# StepperDriver.net
KiCad netlist of a schematic drawn in Altium Designer
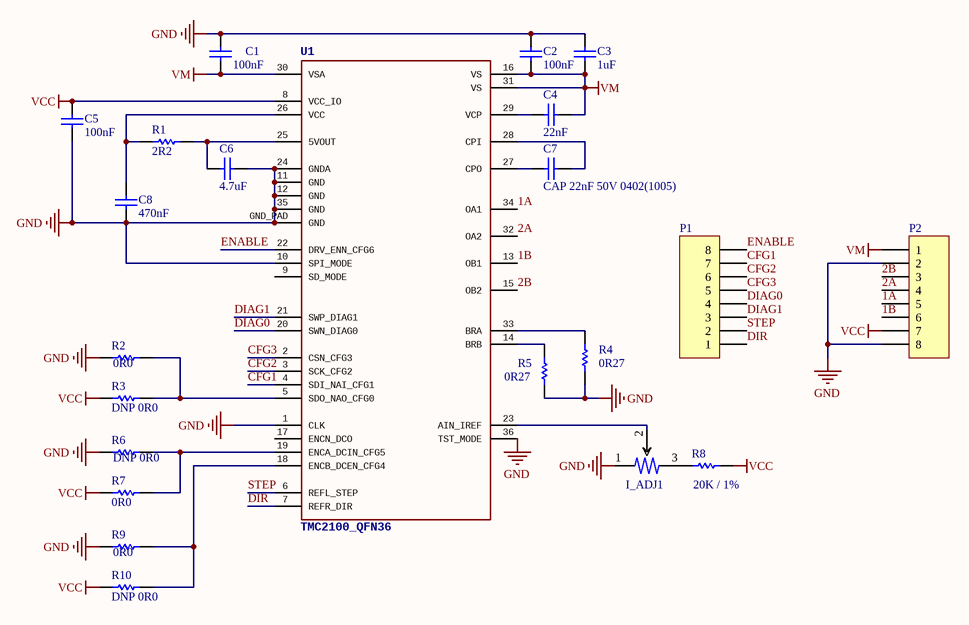
[diagram p0: StepperDriver.SchDoc]

(export (version "E")
  (design (tool "Eeschema 10.0.6"))
  (components
    (comp (ref "C1")
      (value "100nF")
      (footprint "CAPC0402(1005)60_M")
      (description "CAP 100nF 50V ±10% 0402 (1005 Metric) Thickness 0.6mm SMD")
      (fields (field (name "TOLERANCE") "Â±10%"))
      (libsource (lib "Altium Content Vault") (part "CAP"))
    )
    (comp (ref "C2")
      (value "100nF")
      (footprint "CAPC0402(1005)60_M")
      (description "CAP 100nF 50V ±10% 0402 (1005 Metric) Thickness 0.6mm SMD")
      (fields (field (name "TOLERANCE") "Â±10%"))
      (libsource (lib "Altium Content Vault") (part "CAP"))
    )
    (comp (ref "C3")
      (value "1uF")
      (footprint "CAPC0603(1608)100_L")
      (description "CAP 1uF 50V ±10% 0603 (1608 Metric) Thickness 1mm SMD")
      (fields (field (name "TOLERANCE") "Â±10%"))
      (libsource (lib "Altium Content Vault") (part "CAP"))
    )
    (comp (ref "C4")
      (value "22nF")
      (footprint "CAPC0402(1005)60_L")
      (description "CAP 22nF 50V ±5% 0402 (1005 Metric) Thickness 0.6mm SMD")
      (fields (field (name "TOLERANCE") "Â±5%"))
      (libsource (lib "Altium Content Vault") (part "CAP"))
    )
    (comp (ref "C5")
      (value "100nF")
      (footprint "CAPC0402(1005)60_M")
      (description "CAP 100nF 50V ±10% 0402 (1005 Metric) Thickness 0.6mm SMD")
      (fields (field (name "TOLERANCE") "Â±10%"))
      (libsource (lib "Altium Content Vault") (part "CAP"))
    )
    (comp (ref "C6")
      (value "4.7uF")
      (footprint "CAPC0402(1005)60_N")
      (description "CAP 2.2uF 10V ±10% 0402 (1005 Metric) Thickness 0.6mm SMD")
      (fields (field (name "TOLERANCE") "Â±10%"))
      (libsource (lib "Altium Content Vault") (part "CAP"))
    )
    (comp (ref "C7")
      (value "CAP 22nF 50V 0402(1005)")
      (footprint "CAPC0402(1005)60_L")
      (description "CAP 22nF 50V ±5% 0402 (1005 Metric) Thickness 0.6mm SMD")
      (fields (field (name "TOLERANCE") "Â±5%"))
      (libsource (lib "Altium Content Vault") (part "CAP"))
    )
    (comp (ref "C8")
      (value "470nF")
      (footprint "CAPC0402(1005)60_N")
      (description "CAP 470nF 10V ±10% 0402 (1005 Metric) Thickness 0.6mm SMD")
      (fields (field (name "TOLERANCE") "Â±10%"))
      (libsource (lib "Altium Content Vault") (part "CAP"))
    )
    (comp (ref "I_ADJ1")
      (value "PVZ3A Trimmer")
      (footprint "PVZ3A")
      (libsource (lib "Components") (part "PVZ3A Trimmer"))
    )
    (comp (ref "P1")
      (value "Header 8")
      (footprint "HDR1X8")
      (description "Header, 8-Pin")
      (fields (field (name "PUBLISHER") "Altium Limited"))
      (libsource (lib "Miscellaneous Connectors") (part "Header 8"))
    )
    (comp (ref "P2")
      (value "Header 8")
      (footprint "HDR1X8")
      (description "Header, 8-Pin")
      (fields (field (name "PUBLISHER") "Altium Limited"))
      (libsource (lib "") (part "Header 8_1"))
    )
    (comp (ref "R1")
      (value "2R2")
      (footprint "RESC0402(1005)_N")
      (description "2R2 0.063W 5% 0402 (1005 Metric)  SMD")
      (fields (field (name "TOLERANCE") "5 %") (field (name "POWER") "0.063 W"))
      (libsource (lib "Altium Content Vault") (part "RES"))
    )
    (comp (ref "R2")
      (value "0R0")
      (footprint "RESC0402(1005)_M")
      (description "Jumper 0402 (1005 Metric)")
      (fields (field (name "TOLERANCE") "None"))
      (libsource (lib "Altium Content Vault") (part "RES"))
    )
    (comp (ref "R3")
      (value "DNP 0R0")
      (footprint "RESC0402(1005)_M")
      (description "Jumper 0402 (1005 Metric)")
      (fields (field (name "TOLERANCE") "None"))
      (libsource (lib "Altium Content Vault") (part "RES"))
    )
    (comp (ref "R4")
      (value "0R27")
      (footprint "RESC0805(2012)_N")
      (description "Jumper 0805 (2012 Metric)")
      (fields (field (name "TOLERANCE") "None"))
      (libsource (lib "Altium Content Vault") (part "RES"))
    )
    (comp (ref "R5")
      (value "0R27")
      (footprint "RESC0805(2012)_N")
      (description "Jumper 0805 (2012 Metric)")
      (fields (field (name "TOLERANCE") "None"))
      (libsource (lib "Altium Content Vault") (part "RES"))
    )
    (comp (ref "R6")
      (value "DNP 0R0")
      (footprint "RESC0402(1005)_M")
      (description "Jumper 0402 (1005 Metric)")
      (fields (field (name "TOLERANCE") "None"))
      (libsource (lib "Altium Content Vault") (part "RES"))
    )
    (comp (ref "R7")
      (value "0R0")
      (footprint "RESC0402(1005)_M")
      (description "Jumper 0402 (1005 Metric)")
      (fields (field (name "TOLERANCE") "None"))
      (libsource (lib "Altium Content Vault") (part "RES"))
    )
    (comp (ref "R8")
      (value "20K / 1%")
      (footprint "RESC0402(1005)_L")
      (description "0402 (1005 Metric) Chip Resistor")
      (libsource (lib "Altium Content Vault") (part "CMP-1591-00004-1"))
    )
    (comp (ref "R9")
      (value "0R0")
      (footprint "RESC0402(1005)_M")
      (description "Jumper 0402 (1005 Metric)")
      (fields (field (name "TOLERANCE") "None"))
      (libsource (lib "Altium Content Vault") (part "RES"))
    )
    (comp (ref "R10")
      (value "DNP 0R0")
      (footprint "RESC0402(1005)_M")
      (description "Jumper 0402 (1005 Metric)")
      (fields (field (name "TOLERANCE") "None"))
      (libsource (lib "Altium Content Vault") (part "RES"))
    )
    (comp (ref "U1")
      (value "TMC2100_QFN36")
      (footprint "QFN36")
      (libsource (lib "Components") (part "TMC2100_QFN36"))
    )
  )
  (nets
    (net (code "1") (name "/1A") (class "Default")
      (node (ref "P2") (pin "5") (pinfunction "5_5") (pintype "passive"))
      (node (ref "U1") (pin "34") (pinfunction "OA1_34") (pintype "passive"))
    )
    (net (code "2") (name "/1B") (class "Default")
      (node (ref "P2") (pin "6") (pinfunction "6_6") (pintype "passive"))
      (node (ref "U1") (pin "13") (pinfunction "OB1_13") (pintype "passive"))
    )
    (net (code "3") (name "/2A") (class "Default")
      (node (ref "P2") (pin "4") (pinfunction "4_4") (pintype "passive"))
      (node (ref "U1") (pin "32") (pinfunction "OA2_32") (pintype "passive"))
    )
    (net (code "4") (name "/2B") (class "Default")
      (node (ref "P2") (pin "3") (pinfunction "3_3") (pintype "passive"))
      (node (ref "U1") (pin "15") (pinfunction "OB2_15") (pintype "passive"))
    )
    (net (code "5") (name "/CFG1") (class "Default")
      (node (ref "P1") (pin "7") (pinfunction "7_7") (pintype "passive"))
      (node (ref "U1") (pin "4") (pinfunction "SDI_NAI_CFG1_4") (pintype "passive"))
    )
    (net (code "6") (name "/CFG2") (class "Default")
      (node (ref "P1") (pin "6") (pinfunction "6_6") (pintype "passive"))
      (node (ref "U1") (pin "3") (pinfunction "SCK_CFG2_3") (pintype "passive"))
    )
    (net (code "7") (name "/CFG3") (class "Default")
      (node (ref "P1") (pin "5") (pinfunction "5_5") (pintype "passive"))
      (node (ref "U1") (pin "2") (pinfunction "CSN_CFG3_2") (pintype "passive"))
    )
    (net (code "8") (name "/DIAG0") (class "Default")
      (node (ref "P1") (pin "4") (pinfunction "4_4") (pintype "passive"))
      (node (ref "U1") (pin "20") (pinfunction "SWN_DIAG0_20") (pintype "passive"))
    )
    (net (code "9") (name "/DIAG1") (class "Default")
      (node (ref "P1") (pin "3") (pinfunction "3_3") (pintype "passive"))
      (node (ref "U1") (pin "21") (pinfunction "SWP_DIAG1_21") (pintype "passive"))
    )
    (net (code "10") (name "/DIR") (class "Default")
      (node (ref "P1") (pin "1") (pinfunction "1_1") (pintype "passive"))
      (node (ref "U1") (pin "7") (pinfunction "REFR_DIR_7") (pintype "passive"))
    )
    (net (code "11") (name "/ENABLE") (class "Default")
      (node (ref "P1") (pin "8") (pinfunction "8_8") (pintype "passive"))
      (node (ref "U1") (pin "22") (pinfunction "DRV_ENN_CFG6_22") (pintype "passive"))
    )
    (net (code "12") (name "/STEP") (class "Default")
      (node (ref "P1") (pin "2") (pinfunction "2_2") (pintype "passive"))
      (node (ref "U1") (pin "6") (pinfunction "REFL_STEP_6") (pintype "passive"))
    )
    (net (code "13") (name "GND") (class "Default")
      (node (ref "C1") (pin "2") (pinfunction "2_2") (pintype "passive"))
      (node (ref "C2") (pin "2") (pinfunction "2_2") (pintype "passive"))
      (node (ref "C3") (pin "2") (pinfunction "2_2") (pintype "passive"))
      (node (ref "C5") (pin "1") (pinfunction "1_1") (pintype "passive"))
      (node (ref "C6") (pin "1") (pinfunction "1_1") (pintype "passive"))
      (node (ref "C8") (pin "1") (pinfunction "1_1") (pintype "passive"))
      (node (ref "I_ADJ1") (pin "1") (pinfunction "CCW_1") (pintype "passive"))
      (node (ref "P2") (pin "2") (pinfunction "2_2") (pintype "passive"))
      (node (ref "P2") (pin "8") (pinfunction "8_8") (pintype "passive"))
      (node (ref "R2") (pin "1") (pinfunction "1_1") (pintype "passive"))
      (node (ref "R4") (pin "1") (pinfunction "1_1") (pintype "passive"))
      (node (ref "R5") (pin "1") (pinfunction "1_1") (pintype "passive"))
      (node (ref "R6") (pin "1") (pinfunction "1_1") (pintype "passive"))
      (node (ref "R9") (pin "1") (pinfunction "1_1") (pintype "passive"))
      (node (ref "U1") (pin "1") (pinfunction "CLK_1") (pintype "passive"))
      (node (ref "U1") (pin "10") (pinfunction "SPI_MODE_10") (pintype "passive"))
      (node (ref "U1") (pin "11") (pinfunction "GND_11") (pintype "passive"))
      (node (ref "U1") (pin "12") (pinfunction "GND_12") (pintype "passive"))
      (node (ref "U1") (pin "24") (pinfunction "GNDA_24") (pintype "passive"))
      (node (ref "U1") (pin "35") (pinfunction "GND_35") (pintype "passive"))
      (node (ref "U1") (pin "36") (pinfunction "TST_MODE_36") (pintype "passive"))
      (node (ref "U1") (pin "GND_PAD") (pinfunction "GND_GND_PAD") (pintype "passive"))
    )
    (net (code "14") (name "Net-(I_ADJ1-CW)") (class "Default")
      (node (ref "I_ADJ1") (pin "3") (pinfunction "CW_3") (pintype "passive"))
      (node (ref "R8") (pin "1") (pinfunction "1_1") (pintype "passive"))
    )
    (net (code "15") (name "Net-(I_ADJ1-OUT)") (class "Default")
      (node (ref "I_ADJ1") (pin "2") (pinfunction "OUT_2") (pintype "passive"))
      (node (ref "U1") (pin "23") (pinfunction "AIN_IREF_23") (pintype "passive"))
    )
    (net (code "16") (name "Net-(U1-5VOUT)") (class "Default")
      (node (ref "C6") (pin "2") (pinfunction "2_2") (pintype "passive"))
      (node (ref "R1") (pin "2") (pinfunction "2_2") (pintype "passive"))
      (node (ref "U1") (pin "25") (pinfunction "5VOUT_25") (pintype "passive"))
    )
    (net (code "17") (name "Net-(U1-BRA)") (class "Default")
      (node (ref "R4") (pin "2") (pinfunction "2_2") (pintype "passive"))
      (node (ref "U1") (pin "33") (pinfunction "BRA_33") (pintype "passive"))
    )
    (net (code "18") (name "Net-(U1-BRB)") (class "Default")
      (node (ref "R5") (pin "2") (pinfunction "2_2") (pintype "passive"))
      (node (ref "U1") (pin "14") (pinfunction "BRB_14") (pintype "passive"))
    )
    (net (code "19") (name "Net-(U1-CPI)") (class "Default")
      (node (ref "C7") (pin "1") (pinfunction "1_1") (pintype "passive"))
      (node (ref "U1") (pin "28") (pinfunction "CPI_28") (pintype "passive"))
    )
    (net (code "20") (name "Net-(U1-CPO)") (class "Default")
      (node (ref "C7") (pin "2") (pinfunction "2_2") (pintype "passive"))
      (node (ref "U1") (pin "27") (pinfunction "CPO_27") (pintype "passive"))
    )
    (net (code "21") (name "Net-(U1-ENCA_DCIN_CFG5)") (class "Default")
      (node (ref "R6") (pin "2") (pinfunction "2_2") (pintype "passive"))
      (node (ref "R7") (pin "2") (pinfunction "2_2") (pintype "passive"))
      (node (ref "U1") (pin "19") (pinfunction "ENCA_DCIN_CFG5_19") (pintype "passive"))
    )
    (net (code "22") (name "Net-(U1-ENCB_DCEN_CFG4)") (class "Default")
      (node (ref "R10") (pin "2") (pinfunction "2_2") (pintype "passive"))
      (node (ref "R9") (pin "2") (pinfunction "2_2") (pintype "passive"))
      (node (ref "U1") (pin "18") (pinfunction "ENCB_DCEN_CFG4_18") (pintype "passive"))
    )
    (net (code "23") (name "Net-(U1-SDO_NAO_CFG0)") (class "Default")
      (node (ref "R2") (pin "2") (pinfunction "2_2") (pintype "passive"))
      (node (ref "R3") (pin "2") (pinfunction "2_2") (pintype "passive"))
      (node (ref "U1") (pin "5") (pinfunction "SDO_NAO_CFG0_5") (pintype "passive"))
    )
    (net (code "24") (name "Net-(U1-VCC)") (class "Default")
      (node (ref "C8") (pin "2") (pinfunction "2_2") (pintype "passive"))
      (node (ref "R1") (pin "1") (pinfunction "1_1") (pintype "passive"))
      (node (ref "U1") (pin "26") (pinfunction "VCC_26") (pintype "passive"))
    )
    (net (code "25") (name "Net-(U1-VCP)") (class "Default")
      (node (ref "C4") (pin "1") (pinfunction "1_1") (pintype "passive"))
      (node (ref "U1") (pin "29") (pinfunction "VCP_29") (pintype "passive"))
    )
    (net (code "26") (name "VCC") (class "Default")
      (node (ref "C5") (pin "2") (pinfunction "2_2") (pintype "passive"))
      (node (ref "P2") (pin "7") (pinfunction "7_7") (pintype "passive"))
      (node (ref "R10") (pin "1") (pinfunction "1_1") (pintype "passive"))
      (node (ref "R3") (pin "1") (pinfunction "1_1") (pintype "passive"))
      (node (ref "R7") (pin "1") (pinfunction "1_1") (pintype "passive"))
      (node (ref "R8") (pin "2") (pinfunction "2_2") (pintype "passive"))
      (node (ref "U1") (pin "8") (pinfunction "VCC_IO_8") (pintype "passive"))
    )
    (net (code "27") (name "VM") (class "Default")
      (node (ref "C1") (pin "1") (pinfunction "1_1") (pintype "passive"))
      (node (ref "C2") (pin "1") (pinfunction "1_1") (pintype "passive"))
      (node (ref "C3") (pin "1") (pinfunction "1_1") (pintype "passive"))
      (node (ref "C4") (pin "2") (pinfunction "2_2") (pintype "passive"))
      (node (ref "P2") (pin "1") (pinfunction "1_1") (pintype "passive"))
      (node (ref "U1") (pin "16") (pinfunction "VS_16") (pintype "passive"))
      (node (ref "U1") (pin "30") (pinfunction "VSA_30") (pintype "passive"))
      (node (ref "U1") (pin "31") (pinfunction "VS_31") (pintype "passive"))
    )
    (net (code "28") (name "unconnected-(U1-ENCN_DCO-Pad17)") (class "Default")
      (node (ref "U1") (pin "17") (pinfunction "ENCN_DCO_17") (pintype "passive"))
    )
    (net (code "29") (name "unconnected-(U1-SD_MODE-Pad9)") (class "Default")
      (node (ref "U1") (pin "9") (pinfunction "SD_MODE_9") (pintype "passive"))
    )
  )
)
